# ProPrj_acoustic_imager_2026-03-03.net
KiCad netlist of a schematic drawn in EasyEDA Pro
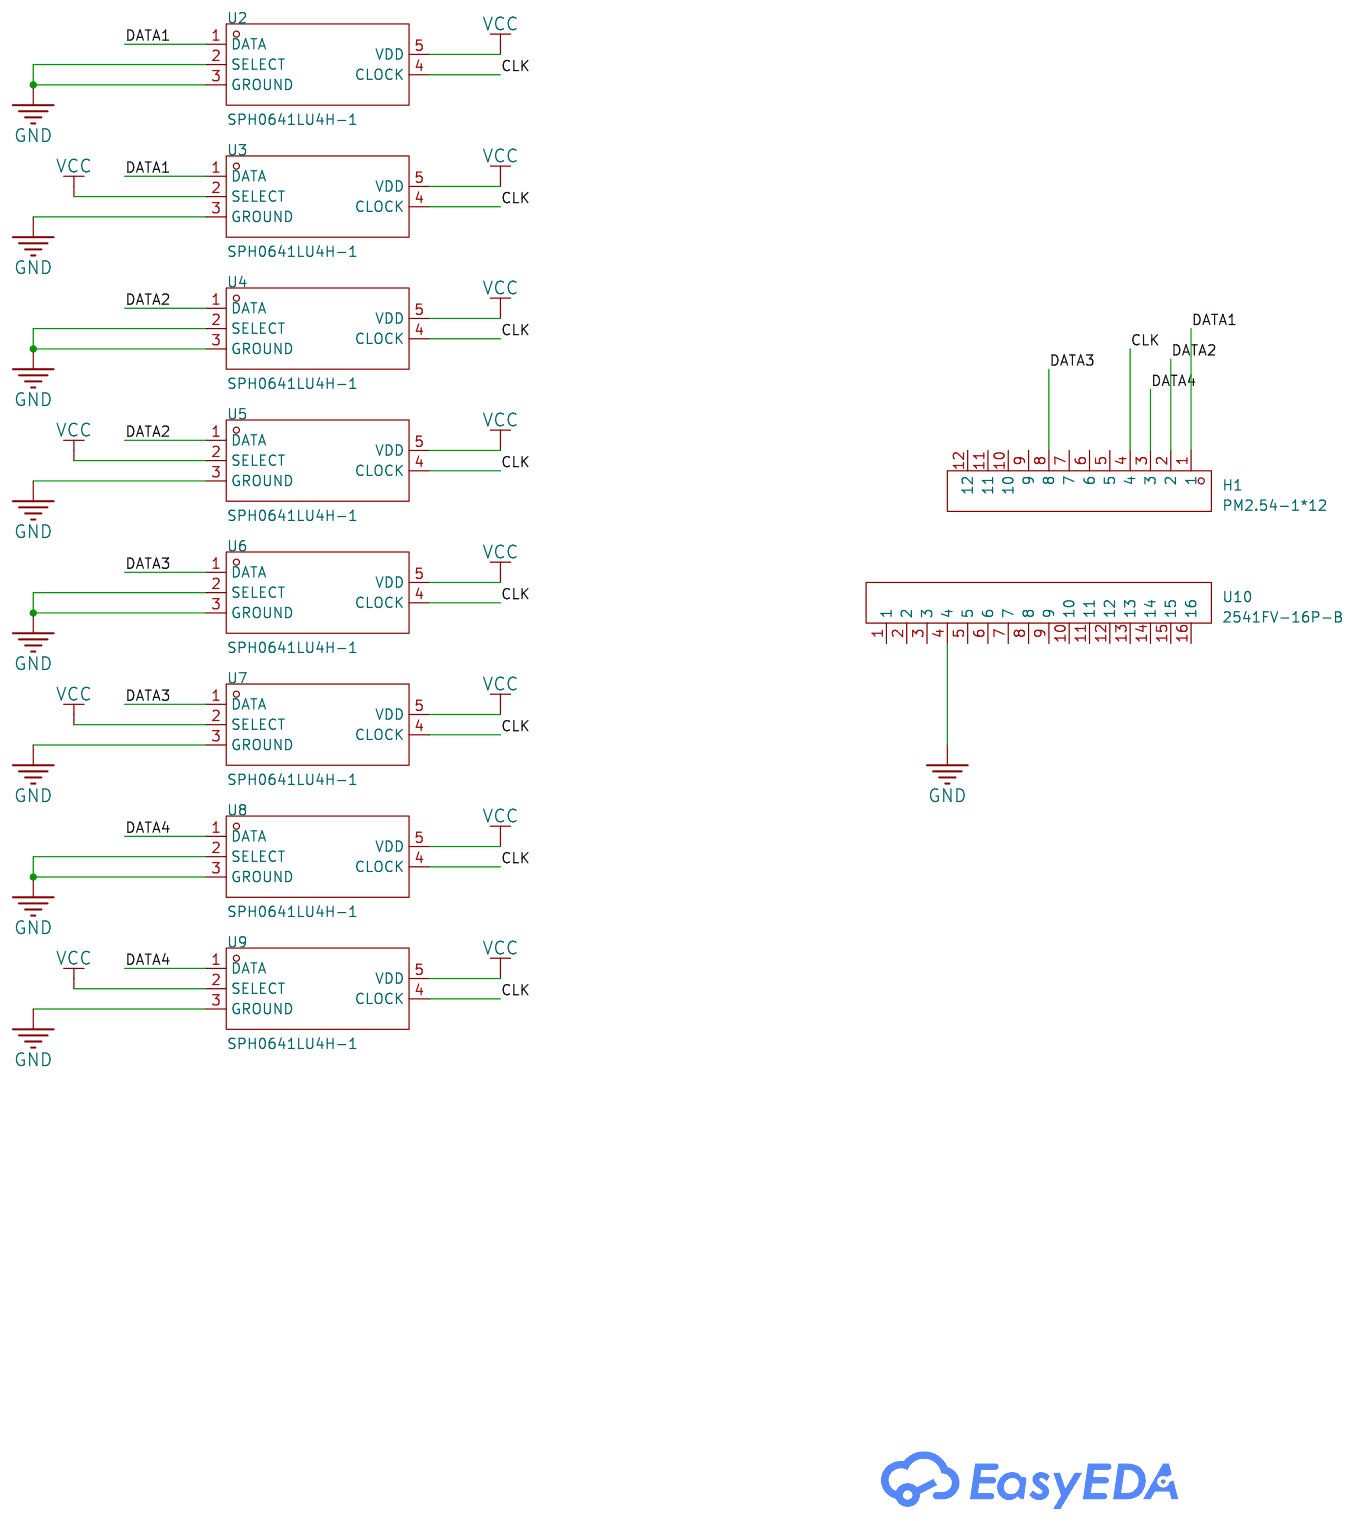
[diagram p0: schematic sheet]

(export (version "E")
  (design (tool "Eeschema 10.0.6"))
  (components
    (comp (ref "H1")
      (value "PM2.54-1*12")
      (footprint "easyedapro:HDR-TH_12P-P2.54-V-F")
      (fields (field (name "Manufacturer") "ZHOURI(洲日)"))
      (libsource (lib "easyedapro") (part "PM2.54-1*12"))
    )
    (comp (ref "U2")
      (value "SPH0641LU4H-1")
      (footprint "easyedapro:MIC-SMD_5P_L3.5-W2.7-P0.82_SPH0641LU4H-1")
      (fields (field (name "Manufacturer") "Knowles(楼氏)"))
      (libsource (lib "easyedapro") (part "SPH0641LU4H-1"))
    )
    (comp (ref "U3")
      (value "SPH0641LU4H-1")
      (footprint "easyedapro:MIC-SMD_5P_L3.5-W2.7-P0.82_SPH0641LU4H-1")
      (fields (field (name "Manufacturer") "Knowles(楼氏)"))
      (libsource (lib "easyedapro") (part "SPH0641LU4H-1"))
    )
    (comp (ref "U4")
      (value "SPH0641LU4H-1")
      (footprint "easyedapro:MIC-SMD_5P_L3.5-W2.7-P0.82_SPH0641LU4H-1")
      (fields (field (name "Manufacturer") "Knowles(楼氏)"))
      (libsource (lib "easyedapro") (part "SPH0641LU4H-1"))
    )
    (comp (ref "U5")
      (value "SPH0641LU4H-1")
      (footprint "easyedapro:MIC-SMD_5P_L3.5-W2.7-P0.82_SPH0641LU4H-1")
      (fields (field (name "Manufacturer") "Knowles(楼氏)"))
      (libsource (lib "easyedapro") (part "SPH0641LU4H-1"))
    )
    (comp (ref "U6")
      (value "SPH0641LU4H-1")
      (footprint "easyedapro:MIC-SMD_5P_L3.5-W2.7-P0.82_SPH0641LU4H-1")
      (fields (field (name "Manufacturer") "Knowles(楼氏)"))
      (libsource (lib "easyedapro") (part "SPH0641LU4H-1"))
    )
    (comp (ref "U7")
      (value "SPH0641LU4H-1")
      (footprint "easyedapro:MIC-SMD_5P_L3.5-W2.7-P0.82_SPH0641LU4H-1")
      (fields (field (name "Manufacturer") "Knowles(楼氏)"))
      (libsource (lib "easyedapro") (part "SPH0641LU4H-1"))
    )
    (comp (ref "U8")
      (value "SPH0641LU4H-1")
      (footprint "easyedapro:MIC-SMD_5P_L3.5-W2.7-P0.82_SPH0641LU4H-1")
      (fields (field (name "Manufacturer") "Knowles(楼氏)"))
      (libsource (lib "easyedapro") (part "SPH0641LU4H-1"))
    )
    (comp (ref "U9")
      (value "SPH0641LU4H-1")
      (footprint "easyedapro:MIC-SMD_5P_L3.5-W2.7-P0.82_SPH0641LU4H-1")
      (fields (field (name "Manufacturer") "Knowles(楼氏)"))
      (libsource (lib "easyedapro") (part "SPH0641LU4H-1"))
    )
    (comp (ref "U10")
      (value "2541FV-16P-B")
      (footprint "easyedapro:HDR-TH_16P-P2.54-V-F-4")
      (fields (field (name "Manufacturer") "HanElectricity(瀚源)"))
      (libsource (lib "easyedapro") (part "2541FV-16P-B"))
    )
  )
  (nets
    (net (code "1") (name "/CLK") (class "Default")
      (node (ref "H1") (pin "4") (pinfunction "4_4") (pintype "unspecified"))
      (node (ref "U2") (pin "4") (pinfunction "CLOCK_4") (pintype "unspecified"))
      (node (ref "U3") (pin "4") (pinfunction "CLOCK_4") (pintype "unspecified"))
      (node (ref "U4") (pin "4") (pinfunction "CLOCK_4") (pintype "unspecified"))
      (node (ref "U5") (pin "4") (pinfunction "CLOCK_4") (pintype "unspecified"))
      (node (ref "U6") (pin "4") (pinfunction "CLOCK_4") (pintype "unspecified"))
      (node (ref "U7") (pin "4") (pinfunction "CLOCK_4") (pintype "unspecified"))
      (node (ref "U8") (pin "4") (pinfunction "CLOCK_4") (pintype "unspecified"))
      (node (ref "U9") (pin "4") (pinfunction "CLOCK_4") (pintype "unspecified"))
    )
    (net (code "2") (name "/DATA1") (class "Default")
      (node (ref "H1") (pin "1") (pinfunction "1_1") (pintype "unspecified"))
      (node (ref "U2") (pin "1") (pinfunction "DATA_1") (pintype "unspecified"))
      (node (ref "U3") (pin "1") (pinfunction "DATA_1") (pintype "unspecified"))
    )
    (net (code "3") (name "/DATA2") (class "Default")
      (node (ref "H1") (pin "2") (pinfunction "2_2") (pintype "unspecified"))
      (node (ref "U4") (pin "1") (pinfunction "DATA_1") (pintype "unspecified"))
      (node (ref "U5") (pin "1") (pinfunction "DATA_1") (pintype "unspecified"))
    )
    (net (code "4") (name "/DATA3") (class "Default")
      (node (ref "H1") (pin "8") (pinfunction "8_8") (pintype "unspecified"))
      (node (ref "U6") (pin "1") (pinfunction "DATA_1") (pintype "unspecified"))
      (node (ref "U7") (pin "1") (pinfunction "DATA_1") (pintype "unspecified"))
    )
    (net (code "5") (name "/DATA4") (class "Default")
      (node (ref "H1") (pin "3") (pinfunction "3_3") (pintype "unspecified"))
      (node (ref "U8") (pin "1") (pinfunction "DATA_1") (pintype "unspecified"))
      (node (ref "U9") (pin "1") (pinfunction "DATA_1") (pintype "unspecified"))
    )
    (net (code "6") (name "GND") (class "Default")
      (node (ref "U10") (pin "4") (pinfunction "4_4") (pintype "unspecified"))
      (node (ref "U2") (pin "2") (pinfunction "SELECT_2") (pintype "unspecified"))
      (node (ref "U2") (pin "3") (pinfunction "GROUND_3") (pintype "unspecified"))
      (node (ref "U3") (pin "3") (pinfunction "GROUND_3") (pintype "unspecified"))
      (node (ref "U4") (pin "2") (pinfunction "SELECT_2") (pintype "unspecified"))
      (node (ref "U4") (pin "3") (pinfunction "GROUND_3") (pintype "unspecified"))
      (node (ref "U5") (pin "3") (pinfunction "GROUND_3") (pintype "unspecified"))
      (node (ref "U6") (pin "2") (pinfunction "SELECT_2") (pintype "unspecified"))
      (node (ref "U6") (pin "3") (pinfunction "GROUND_3") (pintype "unspecified"))
      (node (ref "U7") (pin "3") (pinfunction "GROUND_3") (pintype "unspecified"))
      (node (ref "U8") (pin "2") (pinfunction "SELECT_2") (pintype "unspecified"))
      (node (ref "U8") (pin "3") (pinfunction "GROUND_3") (pintype "unspecified"))
      (node (ref "U9") (pin "3") (pinfunction "GROUND_3") (pintype "unspecified"))
    )
    (net (code "7") (name "VCC") (class "Default")
      (node (ref "U2") (pin "5") (pinfunction "VDD_5") (pintype "unspecified"))
      (node (ref "U3") (pin "2") (pinfunction "SELECT_2") (pintype "unspecified"))
      (node (ref "U3") (pin "5") (pinfunction "VDD_5") (pintype "unspecified"))
      (node (ref "U4") (pin "5") (pinfunction "VDD_5") (pintype "unspecified"))
      (node (ref "U5") (pin "2") (pinfunction "SELECT_2") (pintype "unspecified"))
      (node (ref "U5") (pin "5") (pinfunction "VDD_5") (pintype "unspecified"))
      (node (ref "U6") (pin "5") (pinfunction "VDD_5") (pintype "unspecified"))
      (node (ref "U7") (pin "2") (pinfunction "SELECT_2") (pintype "unspecified"))
      (node (ref "U7") (pin "5") (pinfunction "VDD_5") (pintype "unspecified"))
      (node (ref "U8") (pin "5") (pinfunction "VDD_5") (pintype "unspecified"))
      (node (ref "U9") (pin "2") (pinfunction "SELECT_2") (pintype "unspecified"))
      (node (ref "U9") (pin "5") (pinfunction "VDD_5") (pintype "unspecified"))
    )
    (net (code "8") (name "unconnected-(H1-Pad5)") (class "Default")
      (node (ref "H1") (pin "5") (pinfunction "5_5") (pintype "unspecified"))
    )
    (net (code "9") (name "unconnected-(H1-Pad6)") (class "Default")
      (node (ref "H1") (pin "6") (pinfunction "6_6") (pintype "unspecified"))
    )
    (net (code "10") (name "unconnected-(H1-Pad7)") (class "Default")
      (node (ref "H1") (pin "7") (pinfunction "7_7") (pintype "unspecified"))
    )
    (net (code "11") (name "unconnected-(H1-Pad9)") (class "Default")
      (node (ref "H1") (pin "9") (pinfunction "9_9") (pintype "unspecified"))
    )
    (net (code "12") (name "unconnected-(H1-Pad10)") (class "Default")
      (node (ref "H1") (pin "10") (pinfunction "10_10") (pintype "unspecified"))
    )
    (net (code "13") (name "unconnected-(H1-Pad11)") (class "Default")
      (node (ref "H1") (pin "11") (pinfunction "11_11") (pintype "unspecified"))
    )
    (net (code "14") (name "unconnected-(H1-Pad12)") (class "Default")
      (node (ref "H1") (pin "12") (pinfunction "12_12") (pintype "unspecified"))
    )
    (net (code "15") (name "unconnected-(U10-Pad1)") (class "Default")
      (node (ref "U10") (pin "1") (pinfunction "1_1") (pintype "unspecified"))
    )
    (net (code "16") (name "unconnected-(U10-Pad2)") (class "Default")
      (node (ref "U10") (pin "2") (pinfunction "2_2") (pintype "unspecified"))
    )
    (net (code "17") (name "unconnected-(U10-Pad3)") (class "Default")
      (node (ref "U10") (pin "3") (pinfunction "3_3") (pintype "unspecified"))
    )
    (net (code "18") (name "unconnected-(U10-Pad5)") (class "Default")
      (node (ref "U10") (pin "5") (pinfunction "5_5") (pintype "unspecified"))
    )
    (net (code "19") (name "unconnected-(U10-Pad6)") (class "Default")
      (node (ref "U10") (pin "6") (pinfunction "6_6") (pintype "unspecified"))
    )
    (net (code "20") (name "unconnected-(U10-Pad7)") (class "Default")
      (node (ref "U10") (pin "7") (pinfunction "7_7") (pintype "unspecified"))
    )
    (net (code "21") (name "unconnected-(U10-Pad8)") (class "Default")
      (node (ref "U10") (pin "8") (pinfunction "8_8") (pintype "unspecified"))
    )
    (net (code "22") (name "unconnected-(U10-Pad9)") (class "Default")
      (node (ref "U10") (pin "9") (pinfunction "9_9") (pintype "unspecified"))
    )
    (net (code "23") (name "unconnected-(U10-Pad10)") (class "Default")
      (node (ref "U10") (pin "10") (pinfunction "10_10") (pintype "unspecified"))
    )
    (net (code "24") (name "unconnected-(U10-Pad11)") (class "Default")
      (node (ref "U10") (pin "11") (pinfunction "11_11") (pintype "unspecified"))
    )
    (net (code "25") (name "unconnected-(U10-Pad12)") (class "Default")
      (node (ref "U10") (pin "12") (pinfunction "12_12") (pintype "unspecified"))
    )
    (net (code "26") (name "unconnected-(U10-Pad13)") (class "Default")
      (node (ref "U10") (pin "13") (pinfunction "13_13") (pintype "unspecified"))
    )
    (net (code "27") (name "unconnected-(U10-Pad14)") (class "Default")
      (node (ref "U10") (pin "14") (pinfunction "14_14") (pintype "unspecified"))
    )
    (net (code "28") (name "unconnected-(U10-Pad15)") (class "Default")
      (node (ref "U10") (pin "15") (pinfunction "15_15") (pintype "unspecified"))
    )
    (net (code "29") (name "unconnected-(U10-Pad16)") (class "Default")
      (node (ref "U10") (pin "16") (pinfunction "16_16") (pintype "unspecified"))
    )
  )
)
